# Fume_Absorber.net
KiCad netlist of a schematic drawn in EasyEDA
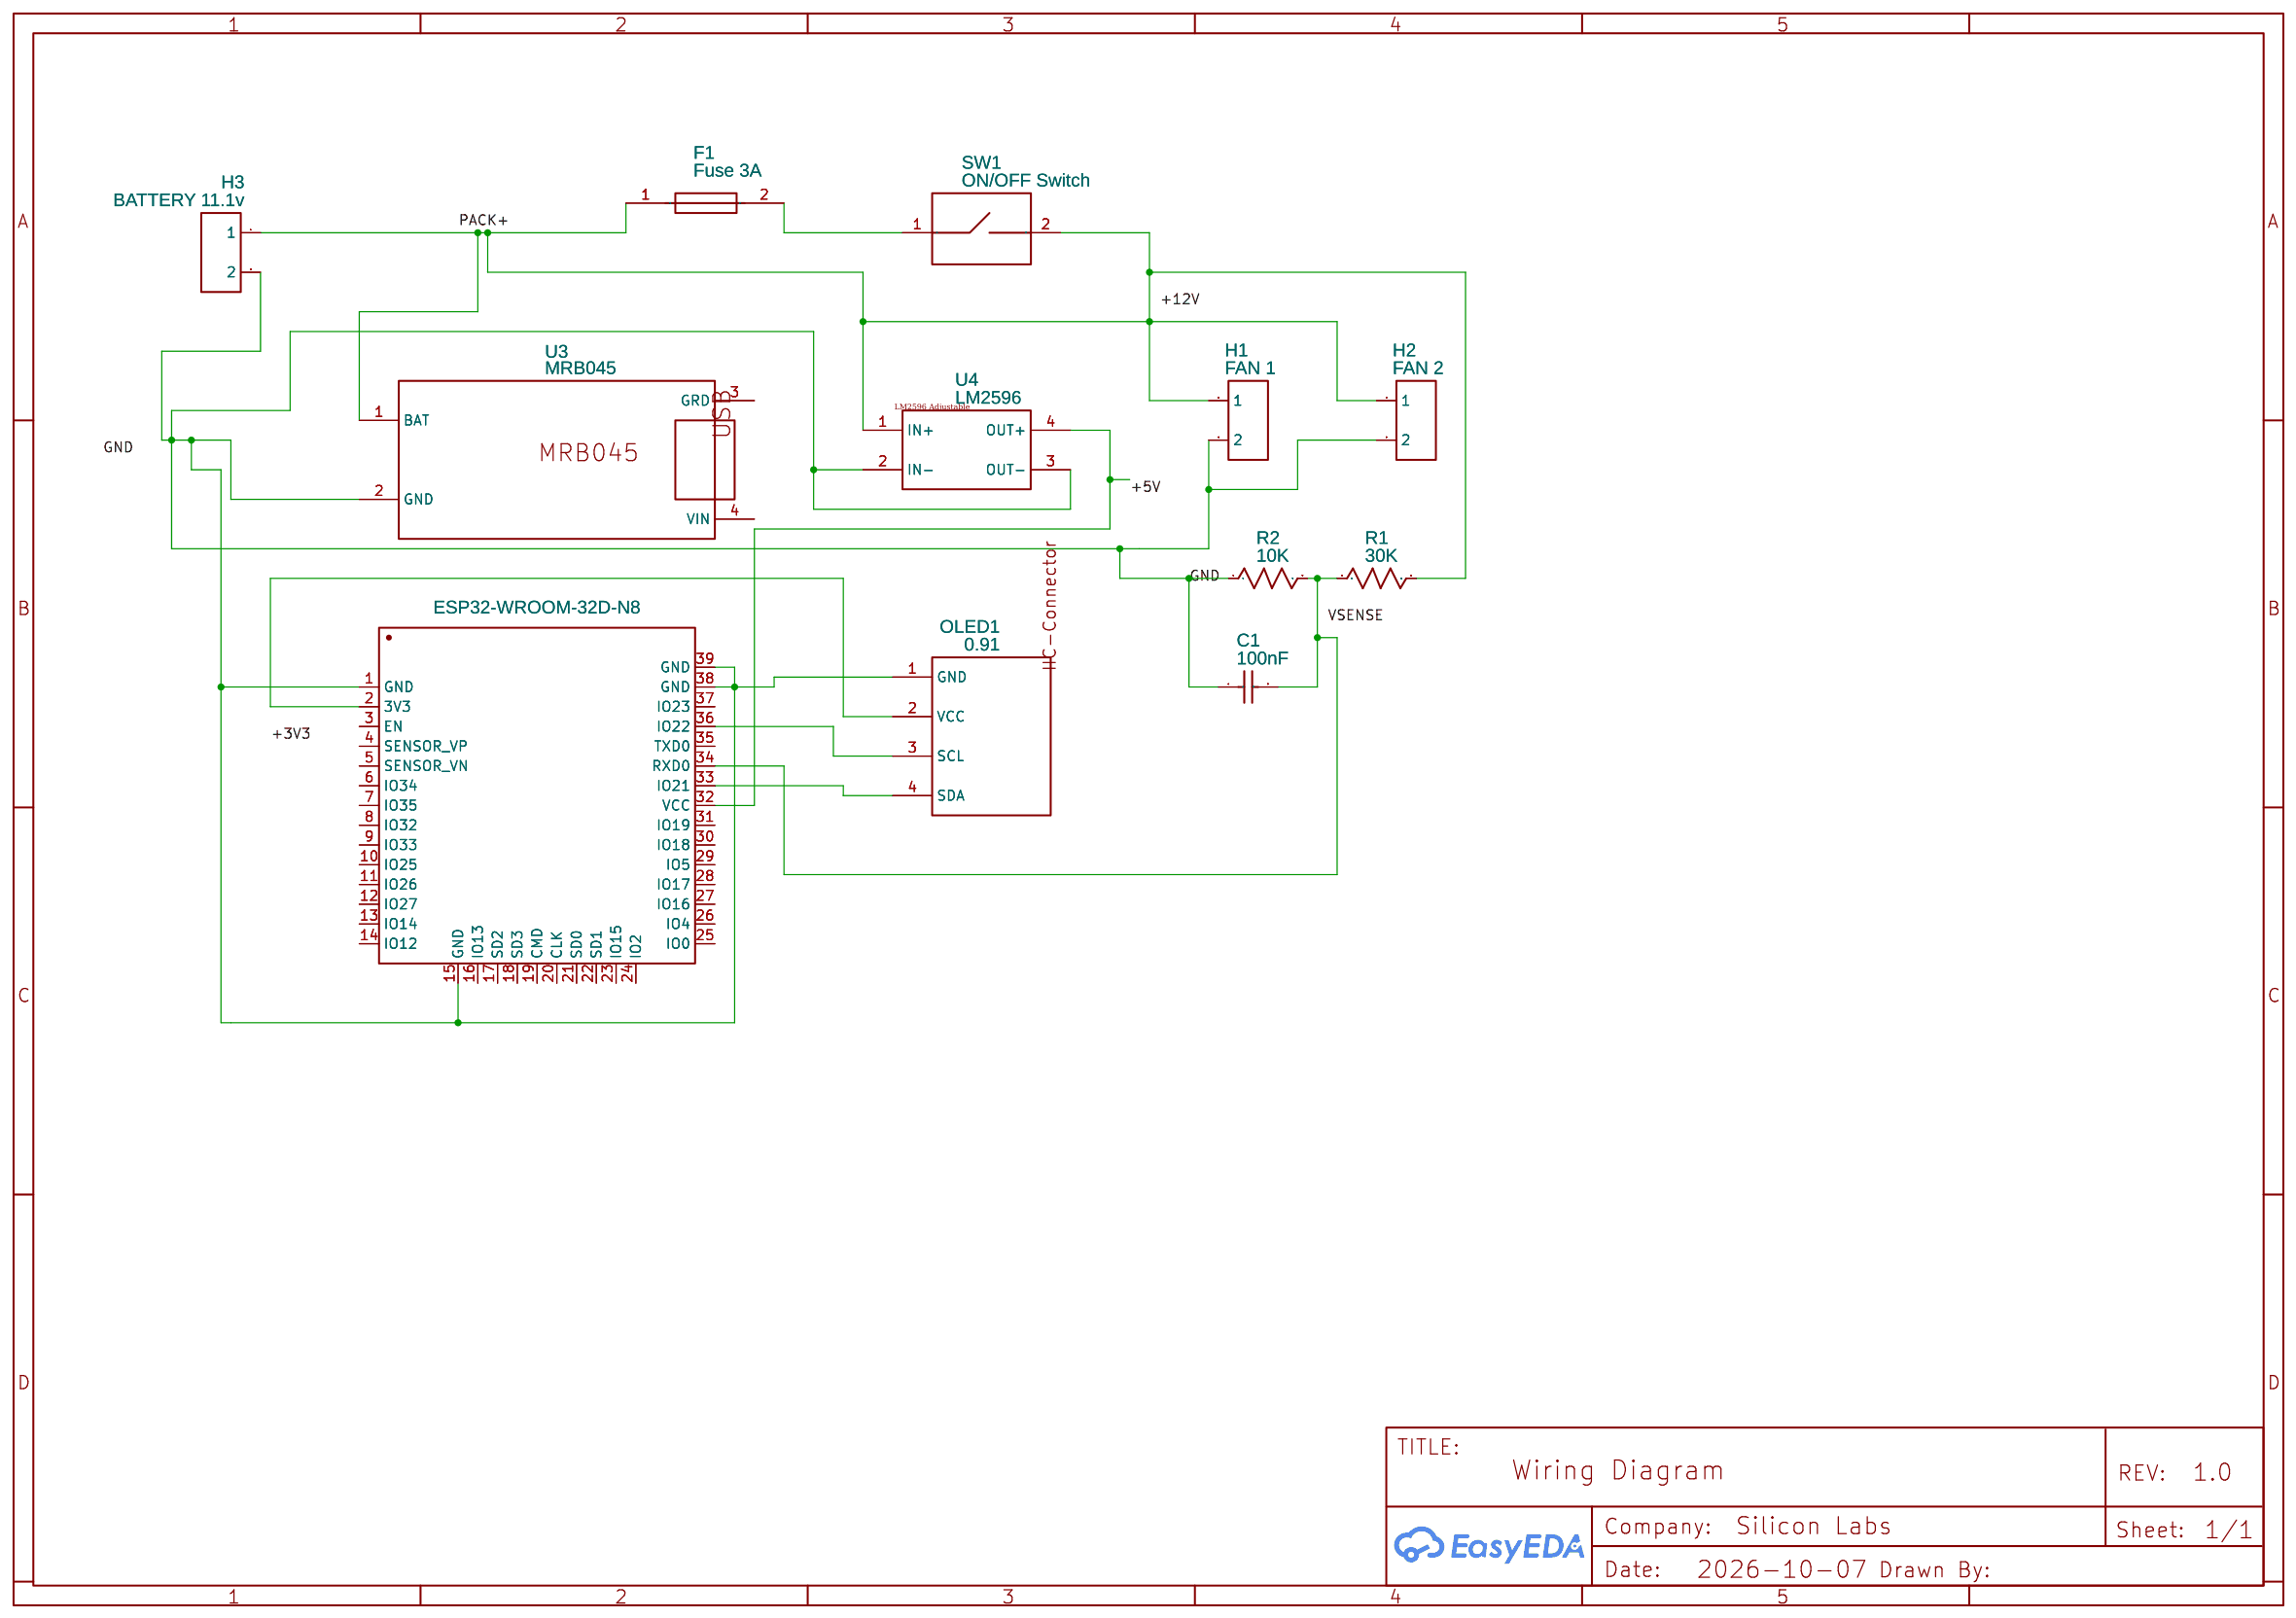
[diagram p0: schematic sheet]

(export (version "E")
  (design (tool "Eeschema 10.0.6"))
  (components
    (comp (ref "C1")
      (value "100nF")
      (fields
        (field (name "Manufacturer Part") "Calibration capacitor100nF（104）100V,5%")
        (field (name "Manufacturer") "ReliaPro")
      )
      (libsource (lib "") (part "Calibration capacitor100nF（104）100V,5%"))
    )
    (comp (ref "F1")
      (value "Fuse 3A")
      (fields (field (name "Manufacturer Part") "汽车中号保险丝座"))
      (libsource (lib "") (part "汽车中号保险丝座"))
    )
    (comp (ref "H1")
      (value "FAN 1")
      (fields
        (field (name "Manufacturer Part") "826629-2")
        (field (name "Manufacturer") "TE Connectivity(泰科电子)")
      )
      (libsource (lib "") (part "Header-Male-2.54_1x2_1"))
    )
    (comp (ref "H2")
      (value "FAN 2")
      (fields
        (field (name "Manufacturer Part") "826629-2")
        (field (name "Manufacturer") "TE Connectivity(泰科电子)")
      )
      (libsource (lib "") (part "Header-Male-2.54_1x2_1"))
    )
    (comp (ref "H3")
      (value "BATTERY 11.1v")
      (fields
        (field (name "Manufacturer Part") "826629-2")
        (field (name "Manufacturer") "TE Connectivity(泰科电子)")
      )
      (libsource (lib "") (part "Header-Male-2.54_1x2"))
    )
    (comp (ref "OLED1")
      (value "0.91")
      (fields (field (name "Manufacturer Part") "0.96OLED_4P_MODULE_JX"))
      (libsource (lib "") (part "0.96OLED_4P_MODULE_JX"))
    )
    (comp (ref "R1") (value "30K") (libsource (lib "") (part "R_0603_US")))
    (comp (ref "R2") (value "10K") (libsource (lib "") (part "R_0603_US")))
    (comp (ref "SW1")
      (value "ON/OFF Switch")
      (fields (field (name "Manufacturer Part") "pu-mts-101 ON-OFF"))
      (libsource (lib "") (part "PU-MTS-101 ON-OFF"))
    )
    (comp (ref "U1")
      (value "ESP32-WROOM-32D-N8")
      (fields (field (name "Manufacturer Part") "ESP32-WROOM-32D-N8-被合并"))
      (libsource (lib "") (part "ESP32-WROOM-32D-N8"))
    )
    (comp (ref "U3") (value "MRB045") (libsource (lib "") (part "MRB045")))
    (comp (ref "U4") (value "LM2596") (libsource (lib "") (part "BuckConverters_LM2596_Adj_PAD")))
  )
  (nets
    (net (code "4") (name "/GND") (class "Default")
      (node (ref "C1") (pin "1") (pinfunction "1_1") (pintype "input"))
      (node (ref "H1") (pin "2") (pinfunction "2_2") (pintype "unspecified"))
      (node (ref "H2") (pin "2") (pinfunction "2_2") (pintype "unspecified"))
      (node (ref "H3") (pin "2") (pinfunction "2_2") (pintype "unspecified"))
      (node (ref "OLED1") (pin "1") (pinfunction "GND_1") (pintype "unspecified"))
      (node (ref "R2") (pin "1") (pinfunction "1_1") (pintype "unspecified"))
      (node (ref "U1") (pin "1") (pinfunction "GND_1") (pintype "unspecified"))
      (node (ref "U1") (pin "15") (pinfunction "GND_15") (pintype "unspecified"))
      (node (ref "U1") (pin "38") (pinfunction "GND_38") (pintype "unspecified"))
      (node (ref "U1") (pin "39") (pinfunction "GND_39") (pintype "unspecified"))
      (node (ref "U3") (pin "2") (pinfunction "GND_2") (pintype "unspecified"))
      (node (ref "U4") (pin "2") (pinfunction "IN-_2") (pintype "unspecified"))
      (node (ref "U4") (pin "3") (pinfunction "OUT-_3") (pintype "unspecified"))
    )
    (net (code "7") (name "Net-(F1-Pad2)") (class "Default")
      (node (ref "F1") (pin "2") (pinfunction "2_2") (pintype "unspecified"))
      (node (ref "SW1") (pin "1") (pinfunction "1_1") (pintype "unspecified"))
    )
    (net (code "8") (name "Net-(OLED1-SCL)") (class "Default")
      (node (ref "OLED1") (pin "3") (pinfunction "SCL_3") (pintype "unspecified"))
      (node (ref "U1") (pin "36") (pinfunction "IO22_36") (pintype "unspecified"))
    )
    (net (code "9") (name "Net-(OLED1-SDA)") (class "Default")
      (node (ref "OLED1") (pin "4") (pinfunction "SDA_4") (pintype "unspecified"))
      (node (ref "U1") (pin "33") (pinfunction "IO21_33") (pintype "unspecified"))
    )
    (net (code "10") (name "Net-(OLED1-VCC)") (class "Default")
      (node (ref "OLED1") (pin "2") (pinfunction "VCC_2") (pintype "unspecified"))
      (node (ref "U1") (pin "2") (pinfunction "3V3_2") (pintype "unspecified"))
    )
    (net (code "11") (name "Net-(U1-RXD0)") (class "Default")
      (node (ref "C1") (pin "2") (pinfunction "2_2") (pintype "input"))
      (node (ref "R1") (pin "1") (pinfunction "1_1") (pintype "unspecified"))
      (node (ref "R2") (pin "2") (pinfunction "2_2") (pintype "unspecified"))
      (node (ref "U1") (pin "34") (pinfunction "RXD0_34") (pintype "unspecified"))
    )
    (net (code "12") (name "Net-(U1-VCC)") (class "Default")
      (node (ref "U1") (pin "32") (pinfunction "VCC_32") (pintype "unspecified"))
      (node (ref "U4") (pin "4") (pinfunction "OUT+_4") (pintype "unspecified"))
    )
    (net (code "13") (name "Net-(U3-BAT)") (class "Default")
      (node (ref "F1") (pin "1") (pinfunction "1_1") (pintype "unspecified"))
      (node (ref "H1") (pin "1") (pinfunction "1_1") (pintype "unspecified"))
      (node (ref "H2") (pin "1") (pinfunction "1_1") (pintype "unspecified"))
      (node (ref "H3") (pin "1") (pinfunction "1_1") (pintype "unspecified"))
      (node (ref "R1") (pin "2") (pinfunction "2_2") (pintype "unspecified"))
      (node (ref "SW1") (pin "2") (pinfunction "2_2") (pintype "unspecified"))
      (node (ref "U3") (pin "1") (pinfunction "BAT_1") (pintype "unspecified"))
      (node (ref "U4") (pin "1") (pinfunction "IN+_1") (pintype "unspecified"))
    )
    (net (code "14") (name "unconnected-(U1-CLK-Pad20)") (class "Default")
      (node (ref "U1") (pin "20") (pinfunction "CLK_20") (pintype "unspecified"))
    )
    (net (code "15") (name "unconnected-(U1-CMD-Pad19)") (class "Default")
      (node (ref "U1") (pin "19") (pinfunction "CMD_19") (pintype "unspecified"))
    )
    (net (code "16") (name "unconnected-(U1-EN-Pad3)") (class "Default")
      (node (ref "U1") (pin "3") (pinfunction "EN_3") (pintype "unspecified"))
    )
    (net (code "17") (name "unconnected-(U1-IO0-Pad25)") (class "Default")
      (node (ref "U1") (pin "25") (pinfunction "IO0_25") (pintype "unspecified"))
    )
    (net (code "18") (name "unconnected-(U1-IO2-Pad24)") (class "Default")
      (node (ref "U1") (pin "24") (pinfunction "IO2_24") (pintype "unspecified"))
    )
    (net (code "19") (name "unconnected-(U1-IO4-Pad26)") (class "Default")
      (node (ref "U1") (pin "26") (pinfunction "IO4_26") (pintype "unspecified"))
    )
    (net (code "20") (name "unconnected-(U1-IO5-Pad29)") (class "Default")
      (node (ref "U1") (pin "29") (pinfunction "IO5_29") (pintype "unspecified"))
    )
    (net (code "21") (name "unconnected-(U1-IO12-Pad14)") (class "Default")
      (node (ref "U1") (pin "14") (pinfunction "IO12_14") (pintype "unspecified"))
    )
    (net (code "22") (name "unconnected-(U1-IO13-Pad16)") (class "Default")
      (node (ref "U1") (pin "16") (pinfunction "IO13_16") (pintype "unspecified"))
    )
    (net (code "23") (name "unconnected-(U1-IO14-Pad13)") (class "Default")
      (node (ref "U1") (pin "13") (pinfunction "IO14_13") (pintype "unspecified"))
    )
    (net (code "24") (name "unconnected-(U1-IO15-Pad23)") (class "Default")
      (node (ref "U1") (pin "23") (pinfunction "IO15_23") (pintype "unspecified"))
    )
    (net (code "25") (name "unconnected-(U1-IO16-Pad27)") (class "Default")
      (node (ref "U1") (pin "27") (pinfunction "IO16_27") (pintype "unspecified"))
    )
    (net (code "26") (name "unconnected-(U1-IO17-Pad28)") (class "Default")
      (node (ref "U1") (pin "28") (pinfunction "IO17_28") (pintype "unspecified"))
    )
    (net (code "27") (name "unconnected-(U1-IO18-Pad30)") (class "Default")
      (node (ref "U1") (pin "30") (pinfunction "IO18_30") (pintype "unspecified"))
    )
    (net (code "28") (name "unconnected-(U1-IO19-Pad31)") (class "Default")
      (node (ref "U1") (pin "31") (pinfunction "IO19_31") (pintype "unspecified"))
    )
    (net (code "29") (name "unconnected-(U1-IO23-Pad37)") (class "Default")
      (node (ref "U1") (pin "37") (pinfunction "IO23_37") (pintype "unspecified"))
    )
    (net (code "30") (name "unconnected-(U1-IO25-Pad10)") (class "Default")
      (node (ref "U1") (pin "10") (pinfunction "IO25_10") (pintype "unspecified"))
    )
    (net (code "31") (name "unconnected-(U1-IO26-Pad11)") (class "Default")
      (node (ref "U1") (pin "11") (pinfunction "IO26_11") (pintype "unspecified"))
    )
    (net (code "32") (name "unconnected-(U1-IO27-Pad12)") (class "Default")
      (node (ref "U1") (pin "12") (pinfunction "IO27_12") (pintype "unspecified"))
    )
    (net (code "33") (name "unconnected-(U1-IO32-Pad8)") (class "Default")
      (node (ref "U1") (pin "8") (pinfunction "IO32_8") (pintype "unspecified"))
    )
    (net (code "34") (name "unconnected-(U1-IO33-Pad9)") (class "Default")
      (node (ref "U1") (pin "9") (pinfunction "IO33_9") (pintype "unspecified"))
    )
    (net (code "35") (name "unconnected-(U1-IO34-Pad6)") (class "Default")
      (node (ref "U1") (pin "6") (pinfunction "IO34_6") (pintype "unspecified"))
    )
    (net (code "36") (name "unconnected-(U1-IO35-Pad7)") (class "Default")
      (node (ref "U1") (pin "7") (pinfunction "IO35_7") (pintype "unspecified"))
    )
    (net (code "37") (name "unconnected-(U1-SD0-Pad21)") (class "Default")
      (node (ref "U1") (pin "21") (pinfunction "SD0_21") (pintype "unspecified"))
    )
    (net (code "38") (name "unconnected-(U1-SD1-Pad22)") (class "Default")
      (node (ref "U1") (pin "22") (pinfunction "SD1_22") (pintype "unspecified"))
    )
    (net (code "39") (name "unconnected-(U1-SD2-Pad17)") (class "Default")
      (node (ref "U1") (pin "17") (pinfunction "SD2_17") (pintype "unspecified"))
    )
    (net (code "40") (name "unconnected-(U1-SD3-Pad18)") (class "Default")
      (node (ref "U1") (pin "18") (pinfunction "SD3_18") (pintype "unspecified"))
    )
    (net (code "41") (name "unconnected-(U1-SENSOR_VN-Pad5)") (class "Default")
      (node (ref "U1") (pin "5") (pinfunction "SENSOR_VN_5") (pintype "unspecified"))
    )
    (net (code "42") (name "unconnected-(U1-SENSOR_VP-Pad4)") (class "Default")
      (node (ref "U1") (pin "4") (pinfunction "SENSOR_VP_4") (pintype "unspecified"))
    )
    (net (code "43") (name "unconnected-(U1-TXD0-Pad35)") (class "Default")
      (node (ref "U1") (pin "35") (pinfunction "TXD0_35") (pintype "unspecified"))
    )
    (net (code "44") (name "unconnected-(U3-GRD-Pad3)") (class "Default")
      (node (ref "U3") (pin "3") (pinfunction "GRD_3") (pintype "unspecified"))
    )
    (net (code "45") (name "unconnected-(U3-VIN-Pad4)") (class "Default")
      (node (ref "U3") (pin "4") (pinfunction "VIN_4") (pintype "unspecified"))
    )
  )
)
